# usb.net
KiCad netlist of a schematic drawn in Altium Designer
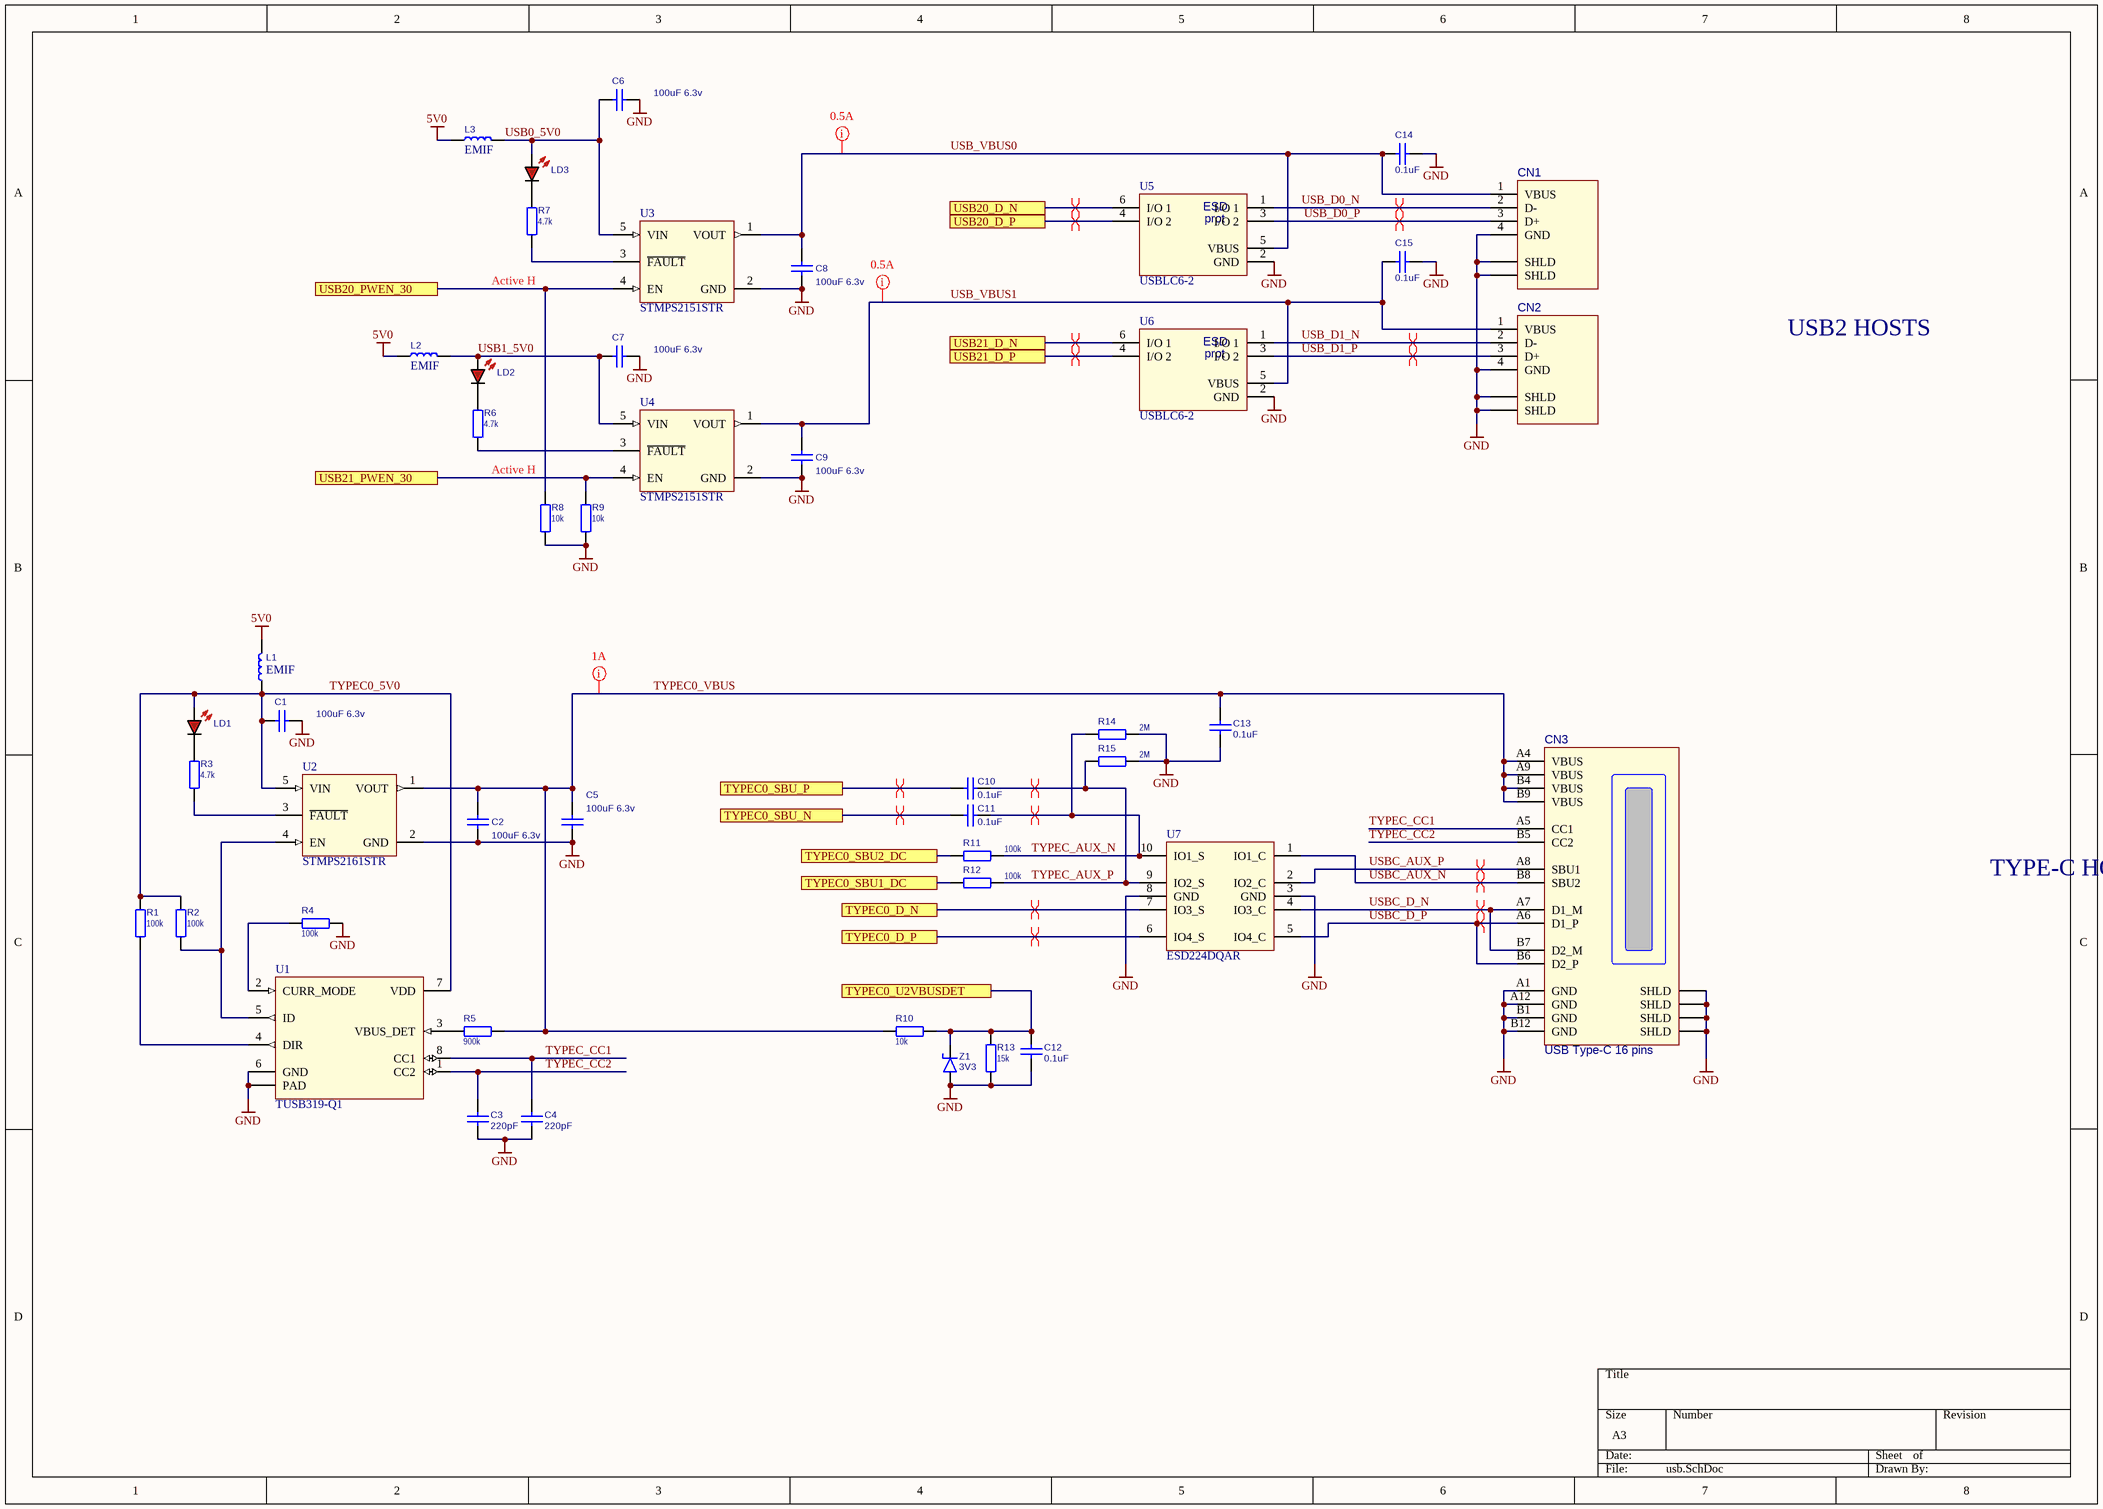
[diagram p0: usb.SchDoc]

(export (version "E")
  (design (tool "Eeschema 10.0.6"))
  (components
    (comp (ref "C1")
      (value "100uF 6.3v")
      (footprint "C1206")
      (description "CAP_NPOL")
      (fields (field (name "Comment") "CL31A107MQHNNNE"))
      (libsource (lib "capacitors") (part "CAP_NPOL"))
    )
    (comp (ref "C2")
      (value "100uF 6.3v")
      (footprint "C1206")
      (description "CAP_NPOL")
      (fields (field (name "Comment") "CL31A107MQHNNNE"))
      (libsource (lib "capacitors") (part "CAP_NPOL"))
    )
    (comp (ref "C3")
      (value "220pF")
      (footprint "Capacitors:C0603")
      (description "CAP_NPOL")
      (fields (field (name "Comment") "CL10C221JB8NNNC"))
      (libsource (lib "capacitors") (part "CAP_NPOL"))
    )
    (comp (ref "C4")
      (value "220pF")
      (footprint "Capacitors:C0603")
      (description "CAP_NPOL")
      (fields (field (name "Comment") "CL10C221JB8NNNC"))
      (libsource (lib "capacitors") (part "CAP_NPOL"))
    )
    (comp (ref "C5")
      (value "100uF 6.3v")
      (footprint "C1206")
      (description "CAP_NPOL")
      (fields (field (name "Comment") "CL31A107MQHNNNE"))
      (libsource (lib "capacitors") (part "CAP_NPOL"))
    )
    (comp (ref "C6")
      (value "100uF 6.3v")
      (footprint "C1206")
      (description "CAP_NPOL")
      (fields (field (name "Comment") "CL31A107MQHNNNE"))
      (libsource (lib "capacitors") (part "CAP_NPOL"))
    )
    (comp (ref "C7")
      (value "100uF 6.3v")
      (footprint "C1206")
      (description "CAP_NPOL")
      (fields (field (name "Comment") "CL31A107MQHNNNE"))
      (libsource (lib "capacitors") (part "CAP_NPOL"))
    )
    (comp (ref "C8")
      (value "100uF 6.3v")
      (footprint "C1206")
      (description "CAP_NPOL")
      (fields (field (name "Comment") "CL31A107MQHNNNE"))
      (libsource (lib "capacitors") (part "CAP_NPOL"))
    )
    (comp (ref "C9")
      (value "100uF 6.3v")
      (footprint "C1206")
      (description "CAP_NPOL")
      (fields (field (name "Comment") "CL31A107MQHNNNE"))
      (libsource (lib "capacitors") (part "CAP_NPOL"))
    )
    (comp (ref "C10")
      (value "0.1uF")
      (footprint "C0603")
      (description "CAP_NPOL")
      (fields (field (name "Comment") "C1608X7R1H104K080AA"))
      (libsource (lib "capacitors") (part "CAP_NPOL"))
    )
    (comp (ref "C11")
      (value "0.1uF")
      (footprint "C0603")
      (description "CAP_NPOL")
      (fields (field (name "Comment") "C1608X7R1H104K080AA"))
      (libsource (lib "capacitors") (part "CAP_NPOL"))
    )
    (comp (ref "C12")
      (value "0.1uF")
      (footprint "Capacitors:C0603")
      (description "CAP_NPOL")
      (fields (field (name "Comment") "C1608X7R1H104K080AA"))
      (libsource (lib "capacitors") (part "CAP_NPOL"))
    )
    (comp (ref "C13")
      (value "0.1uF")
      (footprint "Capacitors:C0603")
      (description "CAP_NPOL")
      (fields (field (name "Comment") "C1608X7R1H104K080AA"))
      (libsource (lib "capacitors") (part "CAP_NPOL"))
    )
    (comp (ref "C14")
      (value "0.1uF")
      (footprint "Capacitors:C0603")
      (description "CAP_NPOL")
      (fields (field (name "Comment") "C1608X7R1H104K080AA"))
      (libsource (lib "capacitors") (part "CAP_NPOL"))
    )
    (comp (ref "C15")
      (value "0.1uF")
      (footprint "Capacitors:C0603")
      (description "CAP_NPOL")
      (fields (field (name "Comment") "C1608X7R1H104K080AA"))
      (libsource (lib "capacitors") (part "CAP_NPOL"))
    )
    (comp (ref "CN1")
      (value "USB Type-A Single")
      (footprint "USB-A-SINGLE")
      (libsource (lib "USB") (part "USB-A-SINGLE"))
    )
    (comp (ref "CN2")
      (value "USB Type-A Single")
      (footprint "USB-A-SINGLE")
      (libsource (lib "USB") (part "USB-A-SINGLE"))
    )
    (comp (ref "CN3")
      (value "USB Type-C 16 pins")
      (footprint "USB-C-16P")
      (libsource (lib "USB") (part "USB-C-16"))
    )
    (comp (ref "L1")
      (value "EMIF")
      (footprint "IND0805")
      (description "IND_WO_IRON")
      (fields (field (name "Comment") "BLM21PG221SN1D"))
      (libsource (lib "inductors") (part "IND_WO_IRON"))
    )
    (comp (ref "L2")
      (value "EMIF")
      (footprint "IND0805")
      (description "IND_WO_IRON")
      (fields (field (name "Comment") "BLM21PG221SN1D"))
      (libsource (lib "inductors") (part "IND_WO_IRON"))
    )
    (comp (ref "L3")
      (value "EMIF")
      (footprint "IND0805")
      (description "IND_WO_IRON")
      (fields (field (name "Comment") "BLM21PG221SN1D"))
      (libsource (lib "inductors") (part "IND_WO_IRON"))
    )
    (comp (ref "LD1")
      (value "LED_R")
      (footprint "Resistors:R0805")
      (description "LED Red")
      (libsource (lib "leds") (part "LED_RED"))
    )
    (comp (ref "LD2")
      (value "LED_R")
      (footprint "Resistors:R0805")
      (description "LED Red")
      (libsource (lib "leds") (part "LED_RED"))
    )
    (comp (ref "LD3")
      (value "LED_R")
      (footprint "Resistors:R0805")
      (description "LED Red")
      (libsource (lib "leds") (part "LED_RED"))
    )
    (comp (ref "R1")
      (value "100k")
      (footprint "R0603")
      (description "RES")
      (libsource (lib "resistors") (part "RESISTOR"))
    )
    (comp (ref "R2")
      (value "100k")
      (footprint "R0603")
      (description "RES")
      (libsource (lib "resistors") (part "RESISTOR"))
    )
    (comp (ref "R3")
      (value "4.7k")
      (footprint "R0603")
      (description "RES")
      (libsource (lib "resistors") (part "RESISTOR"))
    )
    (comp (ref "R4")
      (value "100k")
      (footprint "R0603")
      (description "RES")
      (libsource (lib "resistors") (part "RESISTOR"))
    )
    (comp (ref "R5")
      (value "900k")
      (footprint "R0603")
      (description "RES")
      (libsource (lib "resistors") (part "RESISTOR"))
    )
    (comp (ref "R6")
      (value "4.7k")
      (footprint "R0603")
      (description "RES")
      (libsource (lib "resistors") (part "RESISTOR"))
    )
    (comp (ref "R7")
      (value "4.7k")
      (footprint "R0603")
      (description "RES")
      (libsource (lib "resistors") (part "RESISTOR"))
    )
    (comp (ref "R8")
      (value "10k")
      (footprint "R0603")
      (description "RES")
      (libsource (lib "resistors") (part "RESISTOR"))
    )
    (comp (ref "R9")
      (value "10k")
      (footprint "R0603")
      (description "RES")
      (libsource (lib "resistors") (part "RESISTOR"))
    )
    (comp (ref "R10")
      (value "10k")
      (footprint "R0603")
      (description "RES")
      (libsource (lib "resistors") (part "RESISTOR"))
    )
    (comp (ref "R11")
      (value "100k")
      (footprint "R0603")
      (description "RES")
      (libsource (lib "resistors") (part "RESISTOR"))
    )
    (comp (ref "R12")
      (value "100k")
      (footprint "R0603")
      (description "RES")
      (libsource (lib "resistors") (part "RESISTOR"))
    )
    (comp (ref "R13")
      (value "15k")
      (footprint "R0603")
      (description "RES")
      (libsource (lib "resistors") (part "RESISTOR"))
    )
    (comp (ref "R14")
      (value "2M")
      (footprint "R0603")
      (description "RES")
      (libsource (lib "resistors") (part "RESISTOR"))
    )
    (comp (ref "R15")
      (value "2M")
      (footprint "R0603")
      (description "RES")
      (libsource (lib "resistors") (part "RESISTOR"))
    )
    (comp (ref "U1")
      (value "TUSB319-Q1")
      (footprint "PWSON-8")
      (description "TUSB319-Q1 USB Type-C DFP Port Controller")
      (libsource (lib "TUSB319") (part "TUSB319"))
    )
    (comp (ref "U2")
      (value "STMPS2161STR")
      (footprint "SOT-23-5")
      (libsource (lib "STMPS21x1") (part "STMPS21x1STR"))
    )
    (comp (ref "U3")
      (value "STMPS2151STR")
      (footprint "SOT-23-5")
      (libsource (lib "STMPS21x1") (part "STMPS21x1STR"))
    )
    (comp (ref "U4")
      (value "STMPS2151STR")
      (footprint "SOT-23-5")
      (libsource (lib "STMPS21x1") (part "STMPS21x1STR"))
    )
    (comp (ref "U5")
      (value "USBLC6-2")
      (footprint "SOT-23-6")
      (description "Ultralow capacitance ESD protection")
      (libsource (lib "USBLC6-2") (part "USBLC6-2"))
    )
    (comp (ref "U6")
      (value "USBLC6-2")
      (footprint "SOT-23-6")
      (description "Ultralow capacitance ESD protection")
      (libsource (lib "USBLC6-2") (part "USBLC6-2"))
    )
    (comp (ref "U7")
      (value "ESD224DQAR")
      (footprint "USON-10")
      (description "ESD224 Low Clamping 4-Channel ESD Protection Device for HDMI Interface")
      (libsource (lib "ESD") (part "ESD224"))
    )
    (comp (ref "Z1")
      (value "3V3")
      (footprint "SOD-80C")
      (description "ZENNER")
      (fields (field (name "Comment") "BZV55-C3V3.115"))
      (libsource (lib "diodes") (part "ZENNER_1"))
    )
  )
  (nets
    (net (code "1") (name "/TYPEC0_5V0") (class "Default")
      (node (ref "C1") (pin "2") (pinfunction "2_2") (pintype "passive"))
      (node (ref "L1") (pin "2") (pintype "passive"))
      (node (ref "LD1") (pin "2") (pintype "passive"))
      (node (ref "R1") (pin "2") (pinfunction "2_2") (pintype "passive"))
      (node (ref "R2") (pin "2") (pinfunction "2_2") (pintype "passive"))
      (node (ref "U1") (pin "7") (pinfunction "VDD_7") (pintype "power_in"))
      (node (ref "U2") (pin "5") (pinfunction "VIN_5") (pintype "input"))
    )
    (net (code "2") (name "/TYPEC0_D_N") (class "Default")
      (node (ref "U7") (pin "7") (pinfunction "IO3_S_7") (pintype "passive"))
    )
    (net (code "3") (name "/TYPEC0_D_P") (class "Default")
      (node (ref "U7") (pin "6") (pinfunction "IO4_S_6") (pintype "passive"))
    )
    (net (code "4") (name "/TYPEC0_SBU1_DC") (class "Default")
      (node (ref "R12") (pin "2") (pinfunction "2_2") (pintype "passive"))
    )
    (net (code "5") (name "/TYPEC0_SBU2_DC") (class "Default")
      (node (ref "R11") (pin "2") (pinfunction "2_2") (pintype "passive"))
    )
    (net (code "6") (name "/TYPEC0_SBU_N") (class "Default")
      (node (ref "C11") (pin "2") (pinfunction "2_2") (pintype "passive"))
    )
    (net (code "7") (name "/TYPEC0_SBU_P") (class "Default")
      (node (ref "C10") (pin "2") (pinfunction "2_2") (pintype "passive"))
    )
    (net (code "8") (name "/TYPEC0_U2VBUSDET") (class "Default")
      (node (ref "C12") (pin "1") (pinfunction "1_1") (pintype "passive"))
      (node (ref "R10") (pin "2") (pinfunction "2_2") (pintype "passive"))
      (node (ref "R13") (pin "2") (pinfunction "2_2") (pintype "passive"))
      (node (ref "Z1") (pin "2") (pinfunction "K_2") (pintype "passive"))
    )
    (net (code "9") (name "/TYPEC0_VBUS") (class "Default")
      (node (ref "C13") (pin "1") (pinfunction "1_1") (pintype "passive"))
      (node (ref "C2") (pin "2") (pinfunction "2_2") (pintype "passive"))
      (node (ref "C5") (pin "2") (pinfunction "2_2") (pintype "passive"))
      (node (ref "CN3") (pin "A4") (pinfunction "VBUS_A4") (pintype "passive"))
      (node (ref "CN3") (pin "A9") (pinfunction "VBUS_A9") (pintype "passive"))
      (node (ref "CN3") (pin "B4") (pinfunction "VBUS_B4") (pintype "passive"))
      (node (ref "CN3") (pin "B9") (pinfunction "VBUS_B9") (pintype "passive"))
      (node (ref "R10") (pin "1") (pinfunction "1_1") (pintype "passive"))
      (node (ref "R5") (pin "2") (pinfunction "2_2") (pintype "passive"))
      (node (ref "U2") (pin "1") (pinfunction "VOUT_1") (pintype "output"))
    )
    (net (code "10") (name "/TYPEC_AUX_N") (class "Default")
      (node (ref "C11") (pin "1") (pinfunction "1_1") (pintype "passive"))
      (node (ref "R11") (pin "1") (pinfunction "1_1") (pintype "passive"))
      (node (ref "R14") (pin "2") (pinfunction "2_2") (pintype "passive"))
      (node (ref "U7") (pin "10") (pinfunction "IO1_S_10") (pintype "passive"))
    )
    (net (code "11") (name "/TYPEC_AUX_P") (class "Default")
      (node (ref "C10") (pin "1") (pinfunction "1_1") (pintype "passive"))
      (node (ref "R12") (pin "1") (pinfunction "1_1") (pintype "passive"))
      (node (ref "R15") (pin "2") (pinfunction "2_2") (pintype "passive"))
      (node (ref "U7") (pin "9") (pinfunction "IO2_S_9") (pintype "passive"))
    )
    (net (code "12") (name "/TYPEC_CC1") (class "Default")
      (node (ref "C4") (pin "1") (pinfunction "1_1") (pintype "passive"))
      (node (ref "CN3") (pin "A5") (pinfunction "CC1_A5") (pintype "passive"))
      (node (ref "U1") (pin "8") (pinfunction "CC1_8") (pintype "bidirectional"))
    )
    (net (code "13") (name "/TYPEC_CC2") (class "Default")
      (node (ref "C3") (pin "1") (pinfunction "1_1") (pintype "passive"))
      (node (ref "CN3") (pin "B5") (pinfunction "CC2_B5") (pintype "passive"))
      (node (ref "U1") (pin "1") (pinfunction "CC2_1") (pintype "bidirectional"))
    )
    (net (code "14") (name "/USB0_5V0") (class "Default")
      (node (ref "C6") (pin "2") (pinfunction "2_2") (pintype "passive"))
      (node (ref "L3") (pin "1") (pintype "passive"))
      (node (ref "LD3") (pin "2") (pintype "passive"))
      (node (ref "U3") (pin "5") (pinfunction "VIN_5") (pintype "input"))
    )
    (net (code "15") (name "/USB1_5V0") (class "Default")
      (node (ref "C7") (pin "2") (pinfunction "2_2") (pintype "passive"))
      (node (ref "L2") (pin "1") (pintype "passive"))
      (node (ref "LD2") (pin "2") (pintype "passive"))
      (node (ref "U4") (pin "5") (pinfunction "VIN_5") (pintype "input"))
    )
    (net (code "16") (name "/USB20_D_N") (class "Default")
      (node (ref "U5") (pin "6") (pinfunction "I/O_1_6") (pintype "passive"))
    )
    (net (code "17") (name "/USB20_D_P") (class "Default")
      (node (ref "U5") (pin "4") (pinfunction "I/O_2_4") (pintype "passive"))
    )
    (net (code "18") (name "/USB20_PWEN_30") (class "Default")
      (node (ref "R8") (pin "1") (pinfunction "1_1") (pintype "passive"))
      (node (ref "U3") (pin "4") (pinfunction "EN_4") (pintype "input"))
    )
    (net (code "19") (name "/USB21_D_N") (class "Default")
      (node (ref "U6") (pin "6") (pinfunction "I/O_1_6") (pintype "passive"))
    )
    (net (code "20") (name "/USB21_D_P") (class "Default")
      (node (ref "U6") (pin "4") (pinfunction "I/O_2_4") (pintype "passive"))
    )
    (net (code "21") (name "/USB21_PWEN_30") (class "Default")
      (node (ref "R9") (pin "1") (pinfunction "1_1") (pintype "passive"))
      (node (ref "U4") (pin "4") (pinfunction "EN_4") (pintype "input"))
    )
    (net (code "22") (name "/USBC_AUX_N") (class "Default")
      (node (ref "CN3") (pin "B8") (pinfunction "SBU2_B8") (pintype "passive"))
      (node (ref "U7") (pin "1") (pinfunction "IO1_C_1") (pintype "passive"))
    )
    (net (code "23") (name "/USBC_AUX_P") (class "Default")
      (node (ref "CN3") (pin "A8") (pinfunction "SBU1_A8") (pintype "passive"))
      (node (ref "U7") (pin "2") (pinfunction "IO2_C_2") (pintype "passive"))
    )
    (net (code "24") (name "/USBC_D_N") (class "Default")
      (node (ref "CN3") (pin "A7") (pinfunction "D1_M_A7") (pintype "passive"))
      (node (ref "CN3") (pin "B7") (pinfunction "D2_M_B7") (pintype "passive"))
      (node (ref "U7") (pin "4") (pinfunction "IO3_C_4") (pintype "passive"))
    )
    (net (code "25") (name "/USBC_D_P") (class "Default")
      (node (ref "CN3") (pin "A6") (pinfunction "D1_P_A6") (pintype "passive"))
      (node (ref "CN3") (pin "B6") (pinfunction "D2_P_B6") (pintype "passive"))
      (node (ref "U7") (pin "5") (pinfunction "IO4_C_5") (pintype "passive"))
    )
    (net (code "26") (name "/USB_D0_N") (class "Default")
      (node (ref "CN1") (pin "2") (pinfunction "D-_2") (pintype "passive"))
      (node (ref "U5") (pin "1") (pinfunction "I/O_1_1") (pintype "passive"))
    )
    (net (code "27") (name "/USB_D0_P") (class "Default")
      (node (ref "CN1") (pin "3") (pinfunction "D+_3") (pintype "passive"))
      (node (ref "U5") (pin "3") (pinfunction "I/O_2_3") (pintype "passive"))
    )
    (net (code "28") (name "/USB_D1_N") (class "Default")
      (node (ref "CN2") (pin "2") (pinfunction "D-_2") (pintype "passive"))
      (node (ref "U6") (pin "1") (pinfunction "I/O_1_1") (pintype "passive"))
    )
    (net (code "29") (name "/USB_D1_P") (class "Default")
      (node (ref "CN2") (pin "3") (pinfunction "D+_3") (pintype "passive"))
      (node (ref "U6") (pin "3") (pinfunction "I/O_2_3") (pintype "passive"))
    )
    (net (code "30") (name "/USB_VBUS0") (class "Default")
      (node (ref "C14") (pin "1") (pinfunction "1_1") (pintype "passive"))
      (node (ref "C8") (pin "2") (pinfunction "2_2") (pintype "passive"))
      (node (ref "CN1") (pin "1") (pinfunction "VBUS_1") (pintype "passive"))
      (node (ref "U3") (pin "1") (pinfunction "VOUT_1") (pintype "output"))
      (node (ref "U5") (pin "5") (pinfunction "VBUS_5") (pintype "passive"))
    )
    (net (code "31") (name "/USB_VBUS1") (class "Default")
      (node (ref "C15") (pin "1") (pinfunction "1_1") (pintype "passive"))
      (node (ref "C9") (pin "2") (pinfunction "2_2") (pintype "passive"))
      (node (ref "CN2") (pin "1") (pinfunction "VBUS_1") (pintype "passive"))
      (node (ref "U4") (pin "1") (pinfunction "VOUT_1") (pintype "output"))
      (node (ref "U6") (pin "5") (pinfunction "VBUS_5") (pintype "passive"))
    )
    (net (code "32") (name "5V0") (class "Default")
      (node (ref "L1") (pin "1") (pintype "passive"))
      (node (ref "L2") (pin "2") (pintype "passive"))
      (node (ref "L3") (pin "2") (pintype "passive"))
    )
    (net (code "33") (name "GND") (class "Default")
      (node (ref "C1") (pin "1") (pinfunction "1_1") (pintype "passive"))
      (node (ref "C12") (pin "2") (pinfunction "2_2") (pintype "passive"))
      (node (ref "C13") (pin "2") (pinfunction "2_2") (pintype "passive"))
      (node (ref "C14") (pin "2") (pinfunction "2_2") (pintype "passive"))
      (node (ref "C15") (pin "2") (pinfunction "2_2") (pintype "passive"))
      (node (ref "C2") (pin "1") (pinfunction "1_1") (pintype "passive"))
      (node (ref "C3") (pin "2") (pinfunction "2_2") (pintype "passive"))
      (node (ref "C4") (pin "2") (pinfunction "2_2") (pintype "passive"))
      (node (ref "C5") (pin "1") (pinfunction "1_1") (pintype "passive"))
      (node (ref "C6") (pin "1") (pinfunction "1_1") (pintype "passive"))
      (node (ref "C7") (pin "1") (pinfunction "1_1") (pintype "passive"))
      (node (ref "C8") (pin "1") (pinfunction "1_1") (pintype "passive"))
      (node (ref "C9") (pin "1") (pinfunction "1_1") (pintype "passive"))
      (node (ref "CN1") (pin "4") (pinfunction "GND_4") (pintype "passive"))
      (node (ref "CN1") (pin "5") (pinfunction "SHLD_5") (pintype "passive"))
      (node (ref "CN1") (pin "6") (pinfunction "SHLD_6") (pintype "passive"))
      (node (ref "CN2") (pin "4") (pinfunction "GND_4") (pintype "passive"))
      (node (ref "CN2") (pin "5") (pinfunction "SHLD_5") (pintype "passive"))
      (node (ref "CN2") (pin "6") (pinfunction "SHLD_6") (pintype "passive"))
      (node (ref "CN3") (pin "1") (pinfunction "SHLD_1") (pintype "passive"))
      (node (ref "CN3") (pin "2") (pinfunction "SHLD_2") (pintype "passive"))
      (node (ref "CN3") (pin "3") (pinfunction "SHLD_3") (pintype "passive"))
      (node (ref "CN3") (pin "4") (pinfunction "SHLD_4") (pintype "passive"))
      (node (ref "CN3") (pin "A1") (pinfunction "GND_A1") (pintype "passive"))
      (node (ref "CN3") (pin "A12") (pinfunction "GND_A12") (pintype "passive"))
      (node (ref "CN3") (pin "B1") (pinfunction "GND_B1") (pintype "passive"))
      (node (ref "CN3") (pin "B12") (pinfunction "GND_B12") (pintype "passive"))
      (node (ref "R13") (pin "1") (pinfunction "1_1") (pintype "passive"))
      (node (ref "R14") (pin "1") (pinfunction "1_1") (pintype "passive"))
      (node (ref "R15") (pin "1") (pinfunction "1_1") (pintype "passive"))
      (node (ref "R4") (pin "1") (pinfunction "1_1") (pintype "passive"))
      (node (ref "R8") (pin "2") (pinfunction "2_2") (pintype "passive"))
      (node (ref "R9") (pin "2") (pinfunction "2_2") (pintype "passive"))
      (node (ref "U1") (pin "6") (pinfunction "GND_6") (pintype "power_in"))
      (node (ref "U1") (pin "9") (pinfunction "PAD_9") (pintype "power_in"))
      (node (ref "U2") (pin "2") (pinfunction "GND_2") (pintype "power_in"))
      (node (ref "U3") (pin "2") (pinfunction "GND_2") (pintype "power_in"))
      (node (ref "U4") (pin "2") (pinfunction "GND_2") (pintype "power_in"))
      (node (ref "U5") (pin "2") (pinfunction "GND_2") (pintype "power_in"))
      (node (ref "U6") (pin "2") (pinfunction "GND_2") (pintype "power_in"))
      (node (ref "U7") (pin "3") (pinfunction "GND_3") (pintype "passive"))
      (node (ref "U7") (pin "8") (pinfunction "GND_8") (pintype "passive"))
      (node (ref "Z1") (pin "1") (pinfunction "A_1") (pintype "passive"))
    )
    (net (code "34") (name "Net-(LD1-Pad1)") (class "Default")
      (node (ref "LD1") (pin "1") (pintype "passive"))
      (node (ref "R3") (pin "2") (pinfunction "2_2") (pintype "passive"))
    )
    (net (code "35") (name "Net-(LD2-Pad1)") (class "Default")
      (node (ref "LD2") (pin "1") (pintype "passive"))
      (node (ref "R6") (pin "1") (pinfunction "1_1") (pintype "passive"))
    )
    (net (code "36") (name "Net-(LD3-Pad1)") (class "Default")
      (node (ref "LD3") (pin "1") (pintype "passive"))
      (node (ref "R7") (pin "2") (pinfunction "2_2") (pintype "passive"))
    )
    (net (code "37") (name "Net-(U1-CURR_MODE)") (class "Default")
      (node (ref "R4") (pin "2") (pinfunction "2_2") (pintype "passive"))
      (node (ref "U1") (pin "2") (pinfunction "CURR_MODE_2") (pintype "input"))
    )
    (net (code "38") (name "Net-(U1-DIR)") (class "Default")
      (node (ref "R1") (pin "1") (pinfunction "1_1") (pintype "passive"))
      (node (ref "U1") (pin "4") (pinfunction "DIR_4") (pintype "output"))
    )
    (net (code "39") (name "Net-(U1-ID)") (class "Default")
      (node (ref "R2") (pin "1") (pinfunction "1_1") (pintype "passive"))
      (node (ref "U1") (pin "5") (pinfunction "ID_5") (pintype "output"))
      (node (ref "U2") (pin "4") (pinfunction "EN_4") (pintype "input"))
    )
    (net (code "40") (name "Net-(U1-VBUS_DET)") (class "Default")
      (node (ref "R5") (pin "1") (pinfunction "1_1") (pintype "passive"))
      (node (ref "U1") (pin "3") (pinfunction "VBUS_DET_3") (pintype "input"))
    )
    (net (code "41") (name "Net-(U2-~{FAULT})") (class "Default")
      (node (ref "R3") (pin "1") (pinfunction "1_1") (pintype "passive"))
      (node (ref "U2") (pin "3") (pinfunction "~{FAULT}_3") (pintype "open_collector"))
    )
    (net (code "42") (name "Net-(U3-~{FAULT})") (class "Default")
      (node (ref "R7") (pin "1") (pinfunction "1_1") (pintype "passive"))
      (node (ref "U3") (pin "3") (pinfunction "~{FAULT}_3") (pintype "open_collector"))
    )
    (net (code "43") (name "Net-(U4-~{FAULT})") (class "Default")
      (node (ref "R6") (pin "2") (pinfunction "2_2") (pintype "passive"))
      (node (ref "U4") (pin "3") (pinfunction "~{FAULT}_3") (pintype "open_collector"))
    )
  )
)
